# MRCS-Buckeroo_V1_5.net
KiCad netlist of a schematic drawn in EAGLE
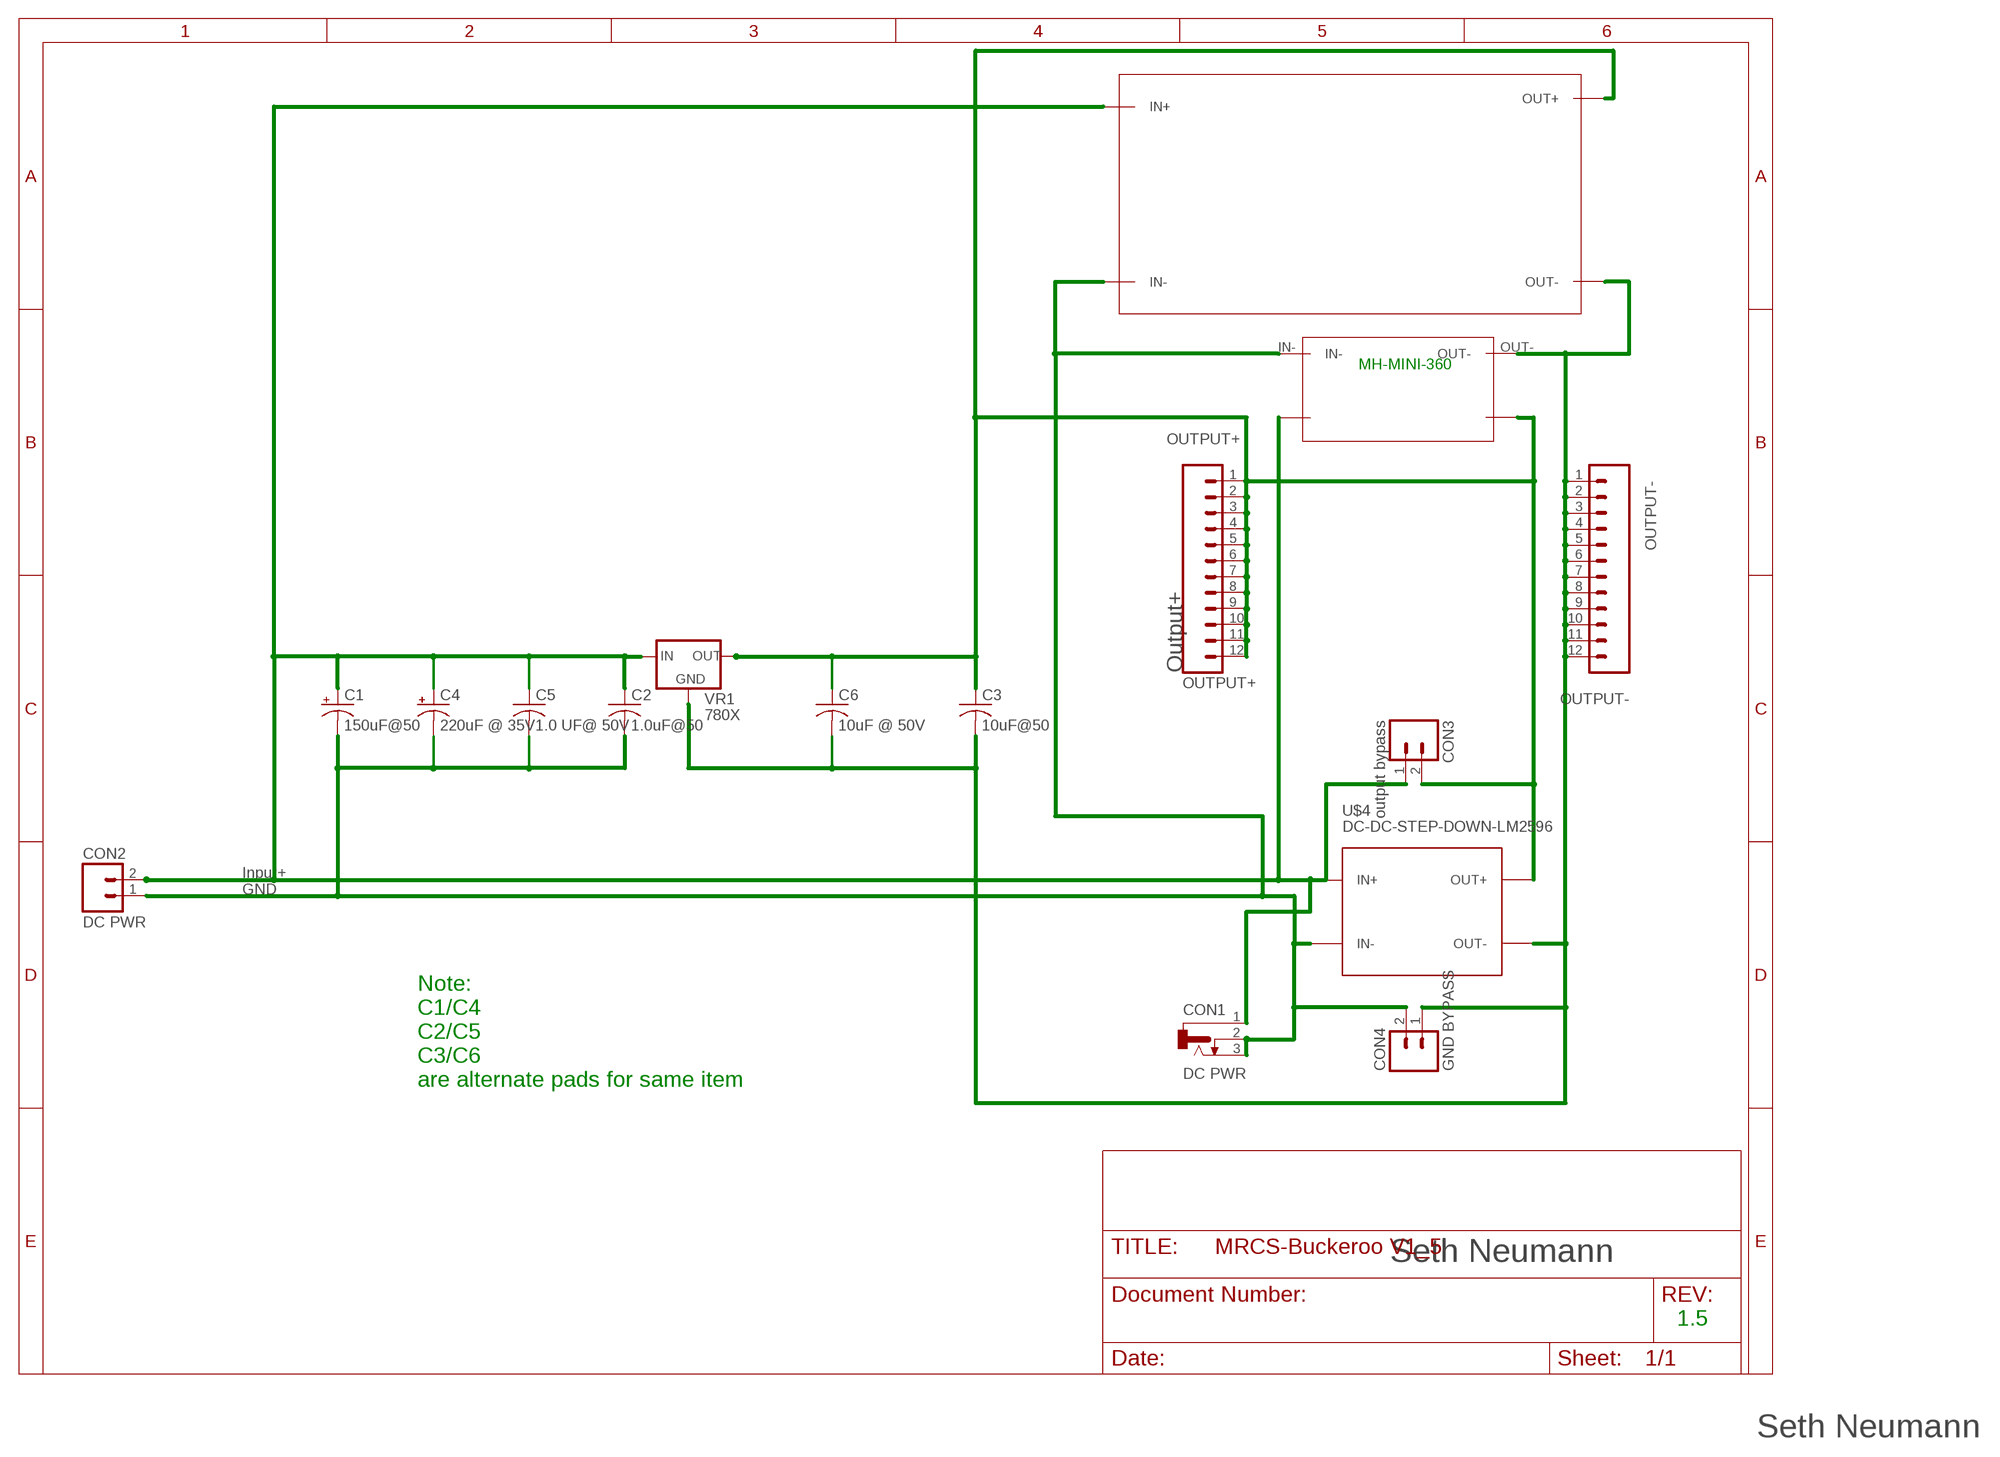
[diagram p0: schematic, sheet 1]

(export (version "E")
  (design (tool "Eeschema 10.0.6"))
  (components
    (comp (ref "C1")
      (value "150uF@50")
      (footprint "eagle-import:E5-10.5")
      (libsource (lib "eagle-import") (part "CAP-POLPTH-5MM"))
    )
    (comp (ref "C2")
      (value "1.0uF@50")
      (footprint "eagle-import:C-PTH-0.100")
      (libsource (lib "eagle-import") (part "CAPPTH2"))
    )
    (comp (ref "C3")
      (value "10uF@50")
      (footprint "eagle-import:C-PTH-0.100")
      (libsource (lib "eagle-import") (part "CAPPTH2"))
    )
    (comp (ref "C4")
      (value "220uF @ 35V")
      (footprint "eagle-import:E2.5-6")
      (libsource (lib "eagle-import") (part "CAP-POLPTH-2.5MM"))
    )
    (comp (ref "C5")
      (value "1.0 UF@ 50V")
      (footprint "eagle-import:C050-024X044")
      (libsource (lib "eagle-import") (part "CAPPTH1"))
    )
    (comp (ref "C6")
      (value "10uF @ 50V")
      (footprint "eagle-import:C050-024X044")
      (libsource (lib "eagle-import") (part "CAPPTH1"))
    )
    (comp (ref "CON1")
      (value "DC PWR")
      (footprint "eagle-import:DCJ0202")
      (libsource (lib "eagle-import") (part "CONNECTOR-DC-POWER-RA"))
    )
    (comp (ref "CON2")
      (value "DC PWR")
      (footprint "eagle-import:SCREWTERMINAL-3.5MM-2_LOCK")
      (libsource (lib "eagle-import") (part "CONNECTOR-M023.5MM-LOCK"))
    )
    (comp (ref "CON3")
      (value "output bypass")
      (footprint "eagle-import:MOLEX-1X2_LOCK")
      (libsource (lib "eagle-import") (part "CONNECTOR-M02MOLEX-1X02-LOCK"))
    )
    (comp (ref "CON4")
      (value "GND BYPASS")
      (footprint "eagle-import:MOLEX-1X2_LOCK")
      (libsource (lib "eagle-import") (part "CONNECTOR-M02MOLEX-1X02-LOCK"))
    )
    (comp (ref "MH-MINI-360")
      (value "MH-MINI-360")
      (footprint "eagle-import:MH-MINI-360")
      (libsource (lib "eagle-import") (part "MH-MINI-360"))
    )
    (comp (ref "OUTPUT+")
      (value "OUTPUT+")
      (footprint "eagle-import:1X12_LOCK")
      (libsource (lib "eagle-import") (part "CONNECTOR-M12LOCK"))
    )
    (comp (ref "OUTPUT-")
      (value "OUTPUT-")
      (footprint "eagle-import:1X12_LOCK")
      (libsource (lib "eagle-import") (part "CONNECTOR-M12LOCK"))
    )
    (comp (ref "U$4")
      (value "DC-DC-STEP-DOWN-LM2596")
      (footprint "eagle-import:DC-DC-STEP-DOWN-LM2596")
      (libsource (lib "eagle-import") (part "DC-DC-STEP-DOWN-LM2596"))
    )
    (comp (ref "U$5")
      (value "XL6009BOARD")
      (footprint "eagle-import:XL6009_BOARD")
      (libsource (lib "eagle-import") (part "XL6009BOARD"))
    )
    (comp (ref "VR1")
      (value "780X")
      (footprint "eagle-import:TO-220-RA")
      (libsource (lib "eagle-import") (part "VREG-?-PTH-RA"))
    )
  )
  (nets
    (net (code "1") (name "Net-(CON2-A)") (class "Default")
      (node (ref "C1") (pin "-") (pinfunction "-_-") (pintype "passive"))
      (node (ref "C2") (pin "2") (pinfunction "2_2") (pintype "passive"))
      (node (ref "C4") (pin "-") (pinfunction "-_-") (pintype "passive"))
      (node (ref "C5") (pin "2") (pinfunction "2_2") (pintype "passive"))
      (node (ref "CON1") (pin "2") (pinfunction "2_2") (pintype "passive"))
      (node (ref "CON1") (pin "3") (pinfunction "3_3") (pintype "passive"))
      (node (ref "CON2") (pin "1") (pinfunction "A_1") (pintype "passive"))
      (node (ref "CON4") (pin "2") (pinfunction "B_2") (pintype "passive"))
      (node (ref "MH-MINI-360") (pin "IN-") (pinfunction "IN-_IN-") (pintype "bidirectional"))
      (node (ref "U$4") (pin "IN-") (pinfunction "IN-_IN-") (pintype "bidirectional"))
      (node (ref "U$5") (pin "IN-") (pinfunction "IN-_IN-") (pintype "bidirectional"))
    )
    (net (code "2") (name "Net-(CON2-B)") (class "Default")
      (node (ref "C1") (pin "+") (pinfunction "+_+") (pintype "passive"))
      (node (ref "C2") (pin "1") (pinfunction "1_1") (pintype "passive"))
      (node (ref "C4") (pin "+") (pinfunction "+_+") (pintype "passive"))
      (node (ref "C5") (pin "1") (pinfunction "1_1") (pintype "passive"))
      (node (ref "CON1") (pin "1") (pinfunction "1_1") (pintype "passive"))
      (node (ref "CON2") (pin "2") (pinfunction "B_2") (pintype "passive"))
      (node (ref "CON3") (pin "1") (pinfunction "A_1") (pintype "passive"))
      (node (ref "MH-MINI-360") (pin "INN+") (pinfunction "INN+_INN+") (pintype "bidirectional"))
      (node (ref "U$4") (pin "IN+") (pinfunction "IN+_IN+") (pintype "bidirectional"))
      (node (ref "U$5") (pin "IN+") (pinfunction "IN+_IN+") (pintype "bidirectional"))
      (node (ref "VR1") (pin "IN") (pinfunction "IN_IN") (pintype "input"))
    )
    (net (code "3") (name "Net-(CON3-B)") (class "Default")
      (node (ref "C3") (pin "1") (pinfunction "1_1") (pintype "passive"))
      (node (ref "C6") (pin "1") (pinfunction "1_1") (pintype "passive"))
      (node (ref "CON3") (pin "2") (pinfunction "B_2") (pintype "passive"))
      (node (ref "MH-MINI-360") (pin "OUTT+") (pinfunction "OUTT+_OUTT+") (pintype "bidirectional"))
      (node (ref "OUTPUT+") (pin "1") (pinfunction "1_1") (pintype "passive"))
      (node (ref "OUTPUT+") (pin "10") (pinfunction "10_10") (pintype "passive"))
      (node (ref "OUTPUT+") (pin "11") (pinfunction "11_11") (pintype "passive"))
      (node (ref "OUTPUT+") (pin "12") (pinfunction "12_12") (pintype "passive"))
      (node (ref "OUTPUT+") (pin "2") (pinfunction "2_2") (pintype "passive"))
      (node (ref "OUTPUT+") (pin "3") (pinfunction "3_3") (pintype "passive"))
      (node (ref "OUTPUT+") (pin "4") (pinfunction "4_4") (pintype "passive"))
      (node (ref "OUTPUT+") (pin "5") (pinfunction "5_5") (pintype "passive"))
      (node (ref "OUTPUT+") (pin "6") (pinfunction "6_6") (pintype "passive"))
      (node (ref "OUTPUT+") (pin "7") (pinfunction "7_7") (pintype "passive"))
      (node (ref "OUTPUT+") (pin "8") (pinfunction "8_8") (pintype "passive"))
      (node (ref "OUTPUT+") (pin "9") (pinfunction "9_9") (pintype "passive"))
      (node (ref "U$4") (pin "OUT+") (pinfunction "OUT+_OUT+") (pintype "bidirectional"))
      (node (ref "U$5") (pin "OUT+") (pinfunction "OUT+_OUT+") (pintype "bidirectional"))
      (node (ref "VR1") (pin "OUT") (pinfunction "OUT_OUT") (pintype "output"))
    )
    (net (code "4") (name "Net-(CON4-A)") (class "Default")
      (node (ref "C3") (pin "2") (pinfunction "2_2") (pintype "passive"))
      (node (ref "C6") (pin "2") (pinfunction "2_2") (pintype "passive"))
      (node (ref "CON4") (pin "1") (pinfunction "A_1") (pintype "passive"))
      (node (ref "MH-MINI-360") (pin "OUT-") (pinfunction "OUT-_OUT-") (pintype "bidirectional"))
      (node (ref "OUTPUT-") (pin "1") (pinfunction "1_1") (pintype "passive"))
      (node (ref "OUTPUT-") (pin "10") (pinfunction "10_10") (pintype "passive"))
      (node (ref "OUTPUT-") (pin "11") (pinfunction "11_11") (pintype "passive"))
      (node (ref "OUTPUT-") (pin "12") (pinfunction "12_12") (pintype "passive"))
      (node (ref "OUTPUT-") (pin "2") (pinfunction "2_2") (pintype "passive"))
      (node (ref "OUTPUT-") (pin "3") (pinfunction "3_3") (pintype "passive"))
      (node (ref "OUTPUT-") (pin "4") (pinfunction "4_4") (pintype "passive"))
      (node (ref "OUTPUT-") (pin "5") (pinfunction "5_5") (pintype "passive"))
      (node (ref "OUTPUT-") (pin "6") (pinfunction "6_6") (pintype "passive"))
      (node (ref "OUTPUT-") (pin "7") (pinfunction "7_7") (pintype "passive"))
      (node (ref "OUTPUT-") (pin "8") (pinfunction "8_8") (pintype "passive"))
      (node (ref "OUTPUT-") (pin "9") (pinfunction "9_9") (pintype "passive"))
      (node (ref "U$4") (pin "OUT-") (pinfunction "OUT-_OUT-") (pintype "bidirectional"))
      (node (ref "U$5") (pin "OUT-") (pinfunction "OUT-_OUT-") (pintype "bidirectional"))
      (node (ref "VR1") (pin "GND") (pinfunction "GND_GND") (pintype "input"))
    )
  )
)
